# quasi_bb_shield_midi.net
KiCad netlist of a schematic drawn in EAGLE
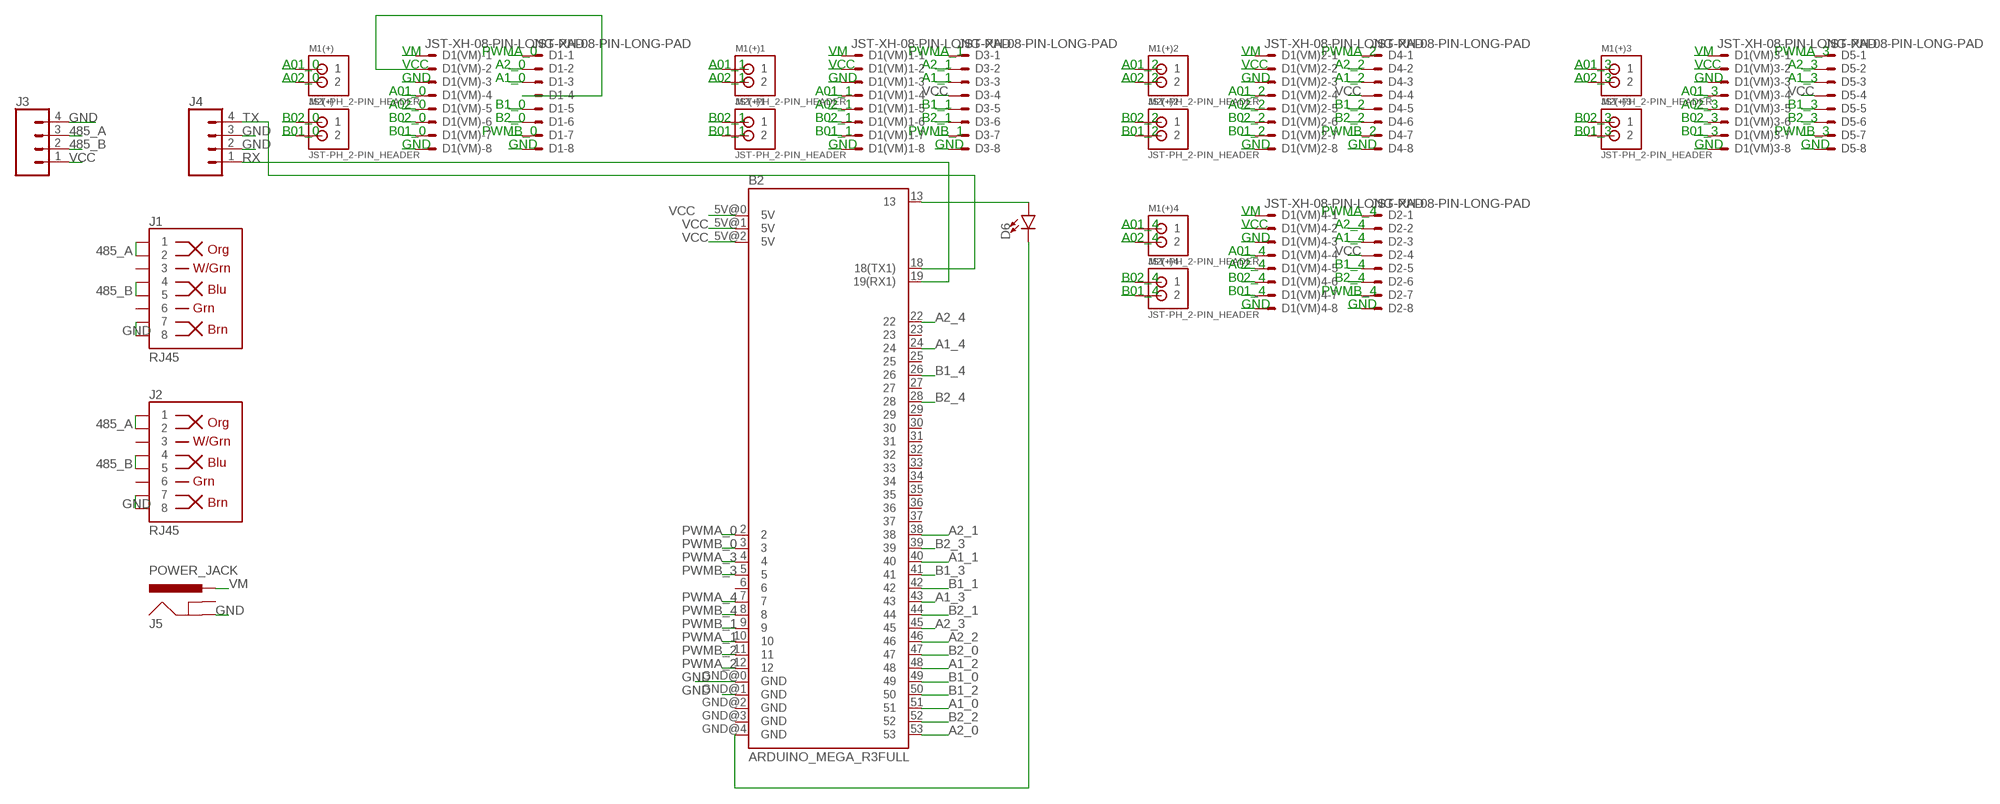
[diagram p0: schematic, sheet 1]

(export (version "E")
  (design (tool "Eeschema 10.0.6"))
  (components
    (comp (ref "B2")
      (value "ARDUINO_MEGA_R3FULL")
      (footprint "eagle-import:ARDUINO_MEGA")
      (libsource (lib "eagle-import") (part "ARDUINO_MEGA_R3FULL"))
    )
    (comp (ref "D1")
      (value "JST-XH-08-PIN-LONG-PAD")
      (footprint "eagle-import:JST-XH-08-PACKAGE-LONG-PAD")
      (libsource (lib "eagle-import") (part "JST-XH-08-PIN-LONG-PAD"))
    )
    (comp (ref "D1(VM)")
      (value "JST-XH-08-PIN-LONG-PAD")
      (footprint "eagle-import:JST-XH-08-PACKAGE-LONG-PAD")
      (libsource (lib "eagle-import") (part "JST-XH-08-PIN-LONG-PAD"))
    )
    (comp (ref "D1(VM)1")
      (value "JST-XH-08-PIN-LONG-PAD")
      (footprint "eagle-import:JST-XH-08-PACKAGE-LONG-PAD")
      (libsource (lib "eagle-import") (part "JST-XH-08-PIN-LONG-PAD"))
    )
    (comp (ref "D1(VM)2")
      (value "JST-XH-08-PIN-LONG-PAD")
      (footprint "eagle-import:JST-XH-08-PACKAGE-LONG-PAD")
      (libsource (lib "eagle-import") (part "JST-XH-08-PIN-LONG-PAD"))
    )
    (comp (ref "D1(VM)3")
      (value "JST-XH-08-PIN-LONG-PAD")
      (footprint "eagle-import:JST-XH-08-PACKAGE-LONG-PAD")
      (libsource (lib "eagle-import") (part "JST-XH-08-PIN-LONG-PAD"))
    )
    (comp (ref "D1(VM)4")
      (value "JST-XH-08-PIN-LONG-PAD")
      (footprint "eagle-import:JST-XH-08-PACKAGE-LONG-PAD")
      (libsource (lib "eagle-import") (part "JST-XH-08-PIN-LONG-PAD"))
    )
    (comp (ref "D2")
      (value "JST-XH-08-PIN-LONG-PAD")
      (footprint "eagle-import:JST-XH-08-PACKAGE-LONG-PAD")
      (libsource (lib "eagle-import") (part "JST-XH-08-PIN-LONG-PAD"))
    )
    (comp (ref "D3")
      (value "JST-XH-08-PIN-LONG-PAD")
      (footprint "eagle-import:JST-XH-08-PACKAGE-LONG-PAD")
      (libsource (lib "eagle-import") (part "JST-XH-08-PIN-LONG-PAD"))
    )
    (comp (ref "D4")
      (value "JST-XH-08-PIN-LONG-PAD")
      (footprint "eagle-import:JST-XH-08-PACKAGE-LONG-PAD")
      (libsource (lib "eagle-import") (part "JST-XH-08-PIN-LONG-PAD"))
    )
    (comp (ref "D5")
      (value "JST-XH-08-PIN-LONG-PAD")
      (footprint "eagle-import:JST-XH-08-PACKAGE-LONG-PAD")
      (libsource (lib "eagle-import") (part "JST-XH-08-PIN-LONG-PAD"))
    )
    (comp (ref "D6")
      (value "LED-3MM-NO_SILK")
      (footprint "eagle-import:LED_3MM-NS")
      (libsource (lib "eagle-import") (part "LED-3MM-NO_SILK"))
    )
    (comp (ref "J1")
      (value "RJ45")
      (footprint "eagle-import:RJ45-8")
      (libsource (lib "eagle-import") (part "RJ45-8"))
    )
    (comp (ref "J2")
      (value "RJ45")
      (footprint "eagle-import:RJ45-8")
      (libsource (lib "eagle-import") (part "RJ45-8"))
    )
    (comp (ref "J3")
      (value "CONN_04")
      (footprint "eagle-import:1X04")
      (libsource (lib "eagle-import") (part "CONN_04"))
    )
    (comp (ref "J4")
      (value "CONN_04")
      (footprint "eagle-import:1X04")
      (libsource (lib "eagle-import") (part "CONN_04"))
    )
    (comp (ref "J5")
      (value "POWER_JACK")
      (footprint "eagle-import:POWER_JACK_PTH")
      (libsource (lib "eagle-import") (part "POWER_JACK"))
    )
    (comp (ref "M1(+)")
      (value "JST-PH_2-PIN_HEADER")
      (footprint "eagle-import:JST_B2B-PH_HEADER")
      (libsource (lib "eagle-import") (part "JST-PH_2-PIN_HEADER"))
    )
    (comp (ref "M1(+)1")
      (value "JST-PH_2-PIN_HEADER")
      (footprint "eagle-import:JST_B2B-PH_HEADER")
      (libsource (lib "eagle-import") (part "JST-PH_2-PIN_HEADER"))
    )
    (comp (ref "M1(+)2")
      (value "JST-PH_2-PIN_HEADER")
      (footprint "eagle-import:JST_B2B-PH_HEADER")
      (libsource (lib "eagle-import") (part "JST-PH_2-PIN_HEADER"))
    )
    (comp (ref "M1(+)3")
      (value "JST-PH_2-PIN_HEADER")
      (footprint "eagle-import:JST_B2B-PH_HEADER")
      (libsource (lib "eagle-import") (part "JST-PH_2-PIN_HEADER"))
    )
    (comp (ref "M1(+)4")
      (value "JST-PH_2-PIN_HEADER")
      (footprint "eagle-import:JST_B2B-PH_HEADER")
      (libsource (lib "eagle-import") (part "JST-PH_2-PIN_HEADER"))
    )
    (comp (ref "M2(+)")
      (value "JST-PH_2-PIN_HEADER")
      (footprint "eagle-import:JST_B2B-PH_HEADER")
      (libsource (lib "eagle-import") (part "JST-PH_2-PIN_HEADER"))
    )
    (comp (ref "M2(+)1")
      (value "JST-PH_2-PIN_HEADER")
      (footprint "eagle-import:JST_B2B-PH_HEADER")
      (libsource (lib "eagle-import") (part "JST-PH_2-PIN_HEADER"))
    )
    (comp (ref "M2(+)2")
      (value "JST-PH_2-PIN_HEADER")
      (footprint "eagle-import:JST_B2B-PH_HEADER")
      (libsource (lib "eagle-import") (part "JST-PH_2-PIN_HEADER"))
    )
    (comp (ref "M2(+)3")
      (value "JST-PH_2-PIN_HEADER")
      (footprint "eagle-import:JST_B2B-PH_HEADER")
      (libsource (lib "eagle-import") (part "JST-PH_2-PIN_HEADER"))
    )
    (comp (ref "M2(+)4")
      (value "JST-PH_2-PIN_HEADER")
      (footprint "eagle-import:JST_B2B-PH_HEADER")
      (libsource (lib "eagle-import") (part "JST-PH_2-PIN_HEADER"))
    )
  )
  (nets
    (net (code "1") (name "/485_A") (class "Default")
      (node (ref "J1") (pin "1") (pinfunction "1_1") (pintype "bidirectional"))
      (node (ref "J1") (pin "2") (pinfunction "2_2") (pintype "bidirectional"))
      (node (ref "J2") (pin "1") (pinfunction "1_1") (pintype "bidirectional"))
      (node (ref "J2") (pin "2") (pinfunction "2_2") (pintype "bidirectional"))
      (node (ref "J3") (pin "3") (pinfunction "3_3") (pintype "passive"))
    )
    (net (code "2") (name "/485_B") (class "Default")
      (node (ref "J1") (pin "4") (pinfunction "4_4") (pintype "bidirectional"))
      (node (ref "J1") (pin "5") (pinfunction "5_5") (pintype "bidirectional"))
      (node (ref "J2") (pin "4") (pinfunction "4_4") (pintype "bidirectional"))
      (node (ref "J2") (pin "5") (pinfunction "5_5") (pintype "bidirectional"))
      (node (ref "J3") (pin "2") (pinfunction "2_2") (pintype "passive"))
    )
    (net (code "3") (name "/A1_0") (class "Default")
      (node (ref "B2") (pin "51") (pinfunction "51_51") (pintype "bidirectional"))
      (node (ref "D1") (pin "3") (pinfunction "S_3") (pintype "passive"))
    )
    (net (code "4") (name "/A01_0") (class "Default")
      (node (ref "D1(VM)") (pin "4") (pinfunction "S_4") (pintype "passive"))
      (node (ref "M1(+)") (pin "P1") (pinfunction "1_P1") (pintype "bidirectional"))
    )
    (net (code "5") (name "/A1_1") (class "Default")
      (node (ref "B2") (pin "40") (pinfunction "40_40") (pintype "bidirectional"))
      (node (ref "D3") (pin "3") (pinfunction "S_3") (pintype "passive"))
    )
    (net (code "6") (name "/A01_1") (class "Default")
      (node (ref "D1(VM)1") (pin "4") (pinfunction "S_4") (pintype "passive"))
      (node (ref "M1(+)1") (pin "P1") (pinfunction "1_P1") (pintype "bidirectional"))
    )
    (net (code "7") (name "/A1_2") (class "Default")
      (node (ref "B2") (pin "48") (pinfunction "48_48") (pintype "bidirectional"))
      (node (ref "D4") (pin "3") (pinfunction "S_3") (pintype "passive"))
    )
    (net (code "8") (name "/A01_2") (class "Default")
      (node (ref "D1(VM)2") (pin "4") (pinfunction "S_4") (pintype "passive"))
      (node (ref "M1(+)2") (pin "P1") (pinfunction "1_P1") (pintype "bidirectional"))
    )
    (net (code "9") (name "/A01_3") (class "Default")
      (node (ref "D1(VM)3") (pin "4") (pinfunction "S_4") (pintype "passive"))
      (node (ref "M1(+)3") (pin "P1") (pinfunction "1_P1") (pintype "bidirectional"))
    )
    (net (code "10") (name "/A1_3") (class "Default")
      (node (ref "B2") (pin "43") (pinfunction "43_43") (pintype "bidirectional"))
      (node (ref "D5") (pin "3") (pinfunction "S_3") (pintype "passive"))
    )
    (net (code "11") (name "/A1_4") (class "Default")
      (node (ref "B2") (pin "24") (pinfunction "24_24") (pintype "bidirectional"))
      (node (ref "D2") (pin "3") (pinfunction "S_3") (pintype "passive"))
    )
    (net (code "12") (name "/A01_4") (class "Default")
      (node (ref "D1(VM)4") (pin "4") (pinfunction "S_4") (pintype "passive"))
      (node (ref "M1(+)4") (pin "P1") (pinfunction "1_P1") (pintype "bidirectional"))
    )
    (net (code "13") (name "/A2_0") (class "Default")
      (node (ref "B2") (pin "53") (pinfunction "53_53") (pintype "bidirectional"))
      (node (ref "D1") (pin "2") (pinfunction "S_2") (pintype "passive"))
    )
    (net (code "14") (name "/A02_0") (class "Default")
      (node (ref "D1(VM)") (pin "5") (pinfunction "S_5") (pintype "passive"))
      (node (ref "M1(+)") (pin "P2") (pinfunction "2_P2") (pintype "bidirectional"))
    )
    (net (code "15") (name "/A02_1") (class "Default")
      (node (ref "D1(VM)1") (pin "5") (pinfunction "S_5") (pintype "passive"))
      (node (ref "M1(+)1") (pin "P2") (pinfunction "2_P2") (pintype "bidirectional"))
    )
    (net (code "16") (name "/A2_1") (class "Default")
      (node (ref "B2") (pin "38") (pinfunction "38_38") (pintype "bidirectional"))
      (node (ref "D3") (pin "2") (pinfunction "S_2") (pintype "passive"))
    )
    (net (code "17") (name "/A2_2") (class "Default")
      (node (ref "B2") (pin "46") (pinfunction "46_46") (pintype "bidirectional"))
      (node (ref "D4") (pin "2") (pinfunction "S_2") (pintype "passive"))
    )
    (net (code "18") (name "/A02_2") (class "Default")
      (node (ref "D1(VM)2") (pin "5") (pinfunction "S_5") (pintype "passive"))
      (node (ref "M1(+)2") (pin "P2") (pinfunction "2_P2") (pintype "bidirectional"))
    )
    (net (code "19") (name "/A2_3") (class "Default")
      (node (ref "B2") (pin "45") (pinfunction "45_45") (pintype "bidirectional"))
      (node (ref "D5") (pin "2") (pinfunction "S_2") (pintype "passive"))
    )
    (net (code "20") (name "/A02_3") (class "Default")
      (node (ref "D1(VM)3") (pin "5") (pinfunction "S_5") (pintype "passive"))
      (node (ref "M1(+)3") (pin "P2") (pinfunction "2_P2") (pintype "bidirectional"))
    )
    (net (code "21") (name "/A02_4") (class "Default")
      (node (ref "D1(VM)4") (pin "5") (pinfunction "S_5") (pintype "passive"))
      (node (ref "M1(+)4") (pin "P2") (pinfunction "2_P2") (pintype "bidirectional"))
    )
    (net (code "22") (name "/A2_4") (class "Default")
      (node (ref "B2") (pin "22") (pinfunction "22_22") (pintype "bidirectional"))
      (node (ref "D2") (pin "2") (pinfunction "S_2") (pintype "passive"))
    )
    (net (code "23") (name "/B1_0") (class "Default")
      (node (ref "B2") (pin "49") (pinfunction "49_49") (pintype "bidirectional"))
      (node (ref "D1") (pin "5") (pinfunction "S_5") (pintype "passive"))
    )
    (net (code "24") (name "/B01_0") (class "Default")
      (node (ref "D1(VM)") (pin "7") (pinfunction "S_7") (pintype "passive"))
      (node (ref "M2(+)") (pin "P2") (pinfunction "2_P2") (pintype "bidirectional"))
    )
    (net (code "25") (name "/B1_1") (class "Default")
      (node (ref "B2") (pin "42") (pinfunction "42_42") (pintype "bidirectional"))
      (node (ref "D3") (pin "5") (pinfunction "S_5") (pintype "passive"))
    )
    (net (code "26") (name "/B01_1") (class "Default")
      (node (ref "D1(VM)1") (pin "7") (pinfunction "S_7") (pintype "passive"))
      (node (ref "M2(+)1") (pin "P2") (pinfunction "2_P2") (pintype "bidirectional"))
    )
    (net (code "27") (name "/B01_2") (class "Default")
      (node (ref "D1(VM)2") (pin "7") (pinfunction "S_7") (pintype "passive"))
      (node (ref "M2(+)2") (pin "P2") (pinfunction "2_P2") (pintype "bidirectional"))
    )
    (net (code "28") (name "/B1_2") (class "Default")
      (node (ref "B2") (pin "50") (pinfunction "50_50") (pintype "bidirectional"))
      (node (ref "D4") (pin "5") (pinfunction "S_5") (pintype "passive"))
    )
    (net (code "29") (name "/B01_3") (class "Default")
      (node (ref "D1(VM)3") (pin "7") (pinfunction "S_7") (pintype "passive"))
      (node (ref "M2(+)3") (pin "P2") (pinfunction "2_P2") (pintype "bidirectional"))
    )
    (net (code "30") (name "/B1_3") (class "Default")
      (node (ref "B2") (pin "41") (pinfunction "41_41") (pintype "bidirectional"))
      (node (ref "D5") (pin "5") (pinfunction "S_5") (pintype "passive"))
    )
    (net (code "31") (name "/B01_4") (class "Default")
      (node (ref "D1(VM)4") (pin "7") (pinfunction "S_7") (pintype "passive"))
      (node (ref "M2(+)4") (pin "P2") (pinfunction "2_P2") (pintype "bidirectional"))
    )
    (net (code "32") (name "/B1_4") (class "Default")
      (node (ref "B2") (pin "26") (pinfunction "26_26") (pintype "bidirectional"))
      (node (ref "D2") (pin "5") (pinfunction "S_5") (pintype "passive"))
    )
    (net (code "33") (name "/B02_0") (class "Default")
      (node (ref "D1(VM)") (pin "6") (pinfunction "S_6") (pintype "passive"))
      (node (ref "M2(+)") (pin "P1") (pinfunction "1_P1") (pintype "bidirectional"))
    )
    (net (code "34") (name "/B2_0") (class "Default")
      (node (ref "B2") (pin "47") (pinfunction "47_47") (pintype "bidirectional"))
      (node (ref "D1") (pin "6") (pinfunction "S_6") (pintype "passive"))
    )
    (net (code "35") (name "/B02_1") (class "Default")
      (node (ref "D1(VM)1") (pin "6") (pinfunction "S_6") (pintype "passive"))
      (node (ref "M2(+)1") (pin "P1") (pinfunction "1_P1") (pintype "bidirectional"))
    )
    (net (code "36") (name "/B2_1") (class "Default")
      (node (ref "B2") (pin "44") (pinfunction "44_44") (pintype "bidirectional"))
      (node (ref "D3") (pin "6") (pinfunction "S_6") (pintype "passive"))
    )
    (net (code "37") (name "/B02_2") (class "Default")
      (node (ref "D1(VM)2") (pin "6") (pinfunction "S_6") (pintype "passive"))
      (node (ref "M2(+)2") (pin "P1") (pinfunction "1_P1") (pintype "bidirectional"))
    )
    (net (code "38") (name "/B2_2") (class "Default")
      (node (ref "B2") (pin "52") (pinfunction "52_52") (pintype "bidirectional"))
      (node (ref "D4") (pin "6") (pinfunction "S_6") (pintype "passive"))
    )
    (net (code "39") (name "/B02_3") (class "Default")
      (node (ref "D1(VM)3") (pin "6") (pinfunction "S_6") (pintype "passive"))
      (node (ref "M2(+)3") (pin "P1") (pinfunction "1_P1") (pintype "bidirectional"))
    )
    (net (code "40") (name "/B2_3") (class "Default")
      (node (ref "B2") (pin "39") (pinfunction "39_39") (pintype "bidirectional"))
      (node (ref "D5") (pin "6") (pinfunction "S_6") (pintype "passive"))
    )
    (net (code "41") (name "/B2_4") (class "Default")
      (node (ref "B2") (pin "28") (pinfunction "28_28") (pintype "bidirectional"))
      (node (ref "D2") (pin "6") (pinfunction "S_6") (pintype "passive"))
    )
    (net (code "42") (name "/B02_4") (class "Default")
      (node (ref "D1(VM)4") (pin "6") (pinfunction "S_6") (pintype "passive"))
      (node (ref "M2(+)4") (pin "P1") (pinfunction "1_P1") (pintype "bidirectional"))
    )
    (net (code "43") (name "/GND") (class "Default")
      (node (ref "B2") (pin "GND@0") (pinfunction "GND_GND@0") (pintype "bidirectional"))
      (node (ref "B2") (pin "GND@1") (pinfunction "GND_GND@1") (pintype "bidirectional"))
      (node (ref "D1") (pin "8") (pinfunction "S_8") (pintype "passive"))
      (node (ref "D1(VM)") (pin "3") (pinfunction "S_3") (pintype "passive"))
      (node (ref "D1(VM)") (pin "8") (pinfunction "S_8") (pintype "passive"))
      (node (ref "D1(VM)1") (pin "3") (pinfunction "S_3") (pintype "passive"))
      (node (ref "D1(VM)1") (pin "8") (pinfunction "S_8") (pintype "passive"))
      (node (ref "D1(VM)2") (pin "3") (pinfunction "S_3") (pintype "passive"))
      (node (ref "D1(VM)2") (pin "8") (pinfunction "S_8") (pintype "passive"))
      (node (ref "D1(VM)3") (pin "3") (pinfunction "S_3") (pintype "passive"))
      (node (ref "D1(VM)3") (pin "8") (pinfunction "S_8") (pintype "passive"))
      (node (ref "D1(VM)4") (pin "3") (pinfunction "S_3") (pintype "passive"))
      (node (ref "D1(VM)4") (pin "8") (pinfunction "S_8") (pintype "passive"))
      (node (ref "D2") (pin "8") (pinfunction "S_8") (pintype "passive"))
      (node (ref "D3") (pin "8") (pinfunction "S_8") (pintype "passive"))
      (node (ref "D4") (pin "8") (pinfunction "S_8") (pintype "passive"))
      (node (ref "D5") (pin "8") (pinfunction "S_8") (pintype "passive"))
      (node (ref "J1") (pin "7") (pinfunction "7_7") (pintype "bidirectional"))
      (node (ref "J1") (pin "8") (pinfunction "8_8") (pintype "bidirectional"))
      (node (ref "J2") (pin "7") (pinfunction "7_7") (pintype "bidirectional"))
      (node (ref "J2") (pin "8") (pinfunction "8_8") (pintype "bidirectional"))
      (node (ref "J3") (pin "4") (pinfunction "4_4") (pintype "passive"))
      (node (ref "J4") (pin "2") (pinfunction "2_2") (pintype "passive"))
      (node (ref "J4") (pin "3") (pinfunction "3_3") (pintype "passive"))
      (node (ref "J5") (pin "GND") (pinfunction "GND_GND") (pintype "bidirectional"))
    )
    (net (code "44") (name "/PWMA_0") (class "Default")
      (node (ref "B2") (pin "2") (pinfunction "2_2") (pintype "bidirectional"))
      (node (ref "D1") (pin "1") (pinfunction "S_1") (pintype "passive"))
    )
    (net (code "45") (name "/PWMA_1") (class "Default")
      (node (ref "B2") (pin "10") (pinfunction "10_10") (pintype "bidirectional"))
      (node (ref "D3") (pin "1") (pinfunction "S_1") (pintype "passive"))
    )
    (net (code "46") (name "/PWMA_2") (class "Default")
      (node (ref "B2") (pin "12") (pinfunction "12_12") (pintype "bidirectional"))
      (node (ref "D4") (pin "1") (pinfunction "S_1") (pintype "passive"))
    )
    (net (code "47") (name "/PWMA_3") (class "Default")
      (node (ref "B2") (pin "4") (pinfunction "4_4") (pintype "bidirectional"))
      (node (ref "D5") (pin "1") (pinfunction "S_1") (pintype "passive"))
    )
    (net (code "48") (name "/PWMA_4") (class "Default")
      (node (ref "B2") (pin "7") (pinfunction "7_7") (pintype "bidirectional"))
      (node (ref "D2") (pin "1") (pinfunction "S_1") (pintype "passive"))
    )
    (net (code "49") (name "/PWMB_0") (class "Default")
      (node (ref "B2") (pin "3") (pinfunction "3_3") (pintype "bidirectional"))
      (node (ref "D1") (pin "7") (pinfunction "S_7") (pintype "passive"))
    )
    (net (code "50") (name "/PWMB_1") (class "Default")
      (node (ref "B2") (pin "9") (pinfunction "9_9") (pintype "bidirectional"))
      (node (ref "D3") (pin "7") (pinfunction "S_7") (pintype "passive"))
    )
    (net (code "51") (name "/PWMB_2") (class "Default")
      (node (ref "B2") (pin "11") (pinfunction "11_11") (pintype "bidirectional"))
      (node (ref "D4") (pin "7") (pinfunction "S_7") (pintype "passive"))
    )
    (net (code "52") (name "/PWMB_3") (class "Default")
      (node (ref "B2") (pin "5") (pinfunction "5_5") (pintype "bidirectional"))
      (node (ref "D5") (pin "7") (pinfunction "S_7") (pintype "passive"))
    )
    (net (code "53") (name "/PWMB_4") (class "Default")
      (node (ref "B2") (pin "8") (pinfunction "8_8") (pintype "bidirectional"))
      (node (ref "D2") (pin "7") (pinfunction "S_7") (pintype "passive"))
    )
    (net (code "54") (name "/RX") (class "Default")
      (node (ref "B2") (pin "19") (pinfunction "19(RX1)_19") (pintype "bidirectional"))
      (node (ref "J4") (pin "1") (pinfunction "1_1") (pintype "passive"))
    )
    (net (code "55") (name "/TX") (class "Default")
      (node (ref "B2") (pin "18") (pinfunction "18(TX1)_18") (pintype "bidirectional"))
      (node (ref "J4") (pin "4") (pinfunction "4_4") (pintype "passive"))
    )
    (net (code "56") (name "/VCC") (class "Default")
      (node (ref "B2") (pin "5V@0") (pinfunction "5V_5V@0") (pintype "bidirectional"))
      (node (ref "B2") (pin "5V@1") (pinfunction "5V_5V@1") (pintype "bidirectional"))
      (node (ref "B2") (pin "5V@2") (pinfunction "5V_5V@2") (pintype "bidirectional"))
      (node (ref "D1") (pin "4") (pinfunction "S_4") (pintype "passive"))
      (node (ref "D1(VM)") (pin "2") (pinfunction "S_2") (pintype "passive"))
      (node (ref "D1(VM)1") (pin "2") (pinfunction "S_2") (pintype "passive"))
      (node (ref "D1(VM)2") (pin "2") (pinfunction "S_2") (pintype "passive"))
      (node (ref "D1(VM)3") (pin "2") (pinfunction "S_2") (pintype "passive"))
      (node (ref "D1(VM)4") (pin "2") (pinfunction "S_2") (pintype "passive"))
      (node (ref "D2") (pin "4") (pinfunction "S_4") (pintype "passive"))
      (node (ref "D3") (pin "4") (pinfunction "S_4") (pintype "passive"))
      (node (ref "D4") (pin "4") (pinfunction "S_4") (pintype "passive"))
      (node (ref "D5") (pin "4") (pinfunction "S_4") (pintype "passive"))
      (node (ref "J3") (pin "1") (pinfunction "1_1") (pintype "passive"))
    )
    (net (code "57") (name "/VM") (class "Default")
      (node (ref "D1(VM)") (pin "1") (pinfunction "S_1") (pintype "passive"))
      (node (ref "D1(VM)1") (pin "1") (pinfunction "S_1") (pintype "passive"))
      (node (ref "D1(VM)2") (pin "1") (pinfunction "S_1") (pintype "passive"))
      (node (ref "D1(VM)3") (pin "1") (pinfunction "S_1") (pintype "passive"))
      (node (ref "D1(VM)4") (pin "1") (pinfunction "S_1") (pintype "passive"))
      (node (ref "J5") (pin "PWR") (pinfunction "PWR_PWR") (pintype "bidirectional"))
    )
    (net (code "58") (name "Net-(B2-Pad13)") (class "Default")
      (node (ref "B2") (pin "13") (pinfunction "13_13") (pintype "bidirectional"))
      (node (ref "D6") (pin "A") (pinfunction "A_A") (pintype "passive"))
    )
    (net (code "59") (name "Net-(D6-C)") (class "Default")
      (node (ref "B2") (pin "GND@4") (pinfunction "GND_GND@4") (pintype "bidirectional"))
      (node (ref "D6") (pin "K") (pinfunction "C_K") (pintype "passive"))
    )
    (net (code "60") (name "unconnected-(B2-GND-PadGND@2)") (class "Default")
      (node (ref "B2") (pin "GND@2") (pinfunction "GND_GND@2") (pintype "bidirectional"))
    )
    (net (code "61") (name "unconnected-(B2-GND-PadGND@3)") (class "Default")
      (node (ref "B2") (pin "GND@3") (pinfunction "GND_GND@3") (pintype "bidirectional"))
    )
    (net (code "62") (name "unconnected-(B2-Pad6)") (class "Default")
      (node (ref "B2") (pin "6") (pinfunction "6_6") (pintype "bidirectional"))
    )
    (net (code "63") (name "unconnected-(B2-Pad23)") (class "Default")
      (node (ref "B2") (pin "23") (pinfunction "23_23") (pintype "bidirectional"))
    )
    (net (code "64") (name "unconnected-(B2-Pad25)") (class "Default")
      (node (ref "B2") (pin "25") (pinfunction "25_25") (pintype "bidirectional"))
    )
    (net (code "65") (name "unconnected-(B2-Pad27)") (class "Default")
      (node (ref "B2") (pin "27") (pinfunction "27_27") (pintype "bidirectional"))
    )
    (net (code "66") (name "unconnected-(B2-Pad29)") (class "Default")
      (node (ref "B2") (pin "29") (pinfunction "29_29") (pintype "bidirectional"))
    )
    (net (code "67") (name "unconnected-(B2-Pad30)") (class "Default")
      (node (ref "B2") (pin "30") (pinfunction "30_30") (pintype "bidirectional"))
    )
    (net (code "68") (name "unconnected-(B2-Pad31)") (class "Default")
      (node (ref "B2") (pin "31") (pinfunction "31_31") (pintype "bidirectional"))
    )
    (net (code "69") (name "unconnected-(B2-Pad32)") (class "Default")
      (node (ref "B2") (pin "32") (pinfunction "32_32") (pintype "bidirectional"))
    )
    (net (code "70") (name "unconnected-(B2-Pad33)") (class "Default")
      (node (ref "B2") (pin "33") (pinfunction "33_33") (pintype "bidirectional"))
    )
    (net (code "71") (name "unconnected-(B2-Pad34)") (class "Default")
      (node (ref "B2") (pin "34") (pinfunction "34_34") (pintype "bidirectional"))
    )
    (net (code "72") (name "unconnected-(B2-Pad35)") (class "Default")
      (node (ref "B2") (pin "35") (pinfunction "35_35") (pintype "bidirectional"))
    )
    (net (code "73") (name "unconnected-(B2-Pad36)") (class "Default")
      (node (ref "B2") (pin "36") (pinfunction "36_36") (pintype "bidirectional"))
    )
    (net (code "74") (name "unconnected-(B2-Pad37)") (class "Default")
      (node (ref "B2") (pin "37") (pinfunction "37_37") (pintype "bidirectional"))
    )
    (net (code "75") (name "unconnected-(J1-Pad3)") (class "Default")
      (node (ref "J1") (pin "3") (pinfunction "3_3") (pintype "bidirectional"))
    )
    (net (code "76") (name "unconnected-(J1-Pad6)") (class "Default")
      (node (ref "J1") (pin "6") (pinfunction "6_6") (pintype "bidirectional"))
    )
    (net (code "77") (name "unconnected-(J2-Pad3)") (class "Default")
      (node (ref "J2") (pin "3") (pinfunction "3_3") (pintype "bidirectional"))
    )
    (net (code "78") (name "unconnected-(J2-Pad6)") (class "Default")
      (node (ref "J2") (pin "6") (pinfunction "6_6") (pintype "bidirectional"))
    )
    (net (code "79") (name "unconnected-(J5-PadGNDBREAK)") (class "Default")
      (node (ref "J5") (pin "GNDBREAK") (pinfunction "GNDBREAK_GNDBREAK") (pintype "bidirectional"))
    )
  )
)
